# Mainboard_-_Prototype_1.net
KiCad netlist of a schematic drawn in EAGLE
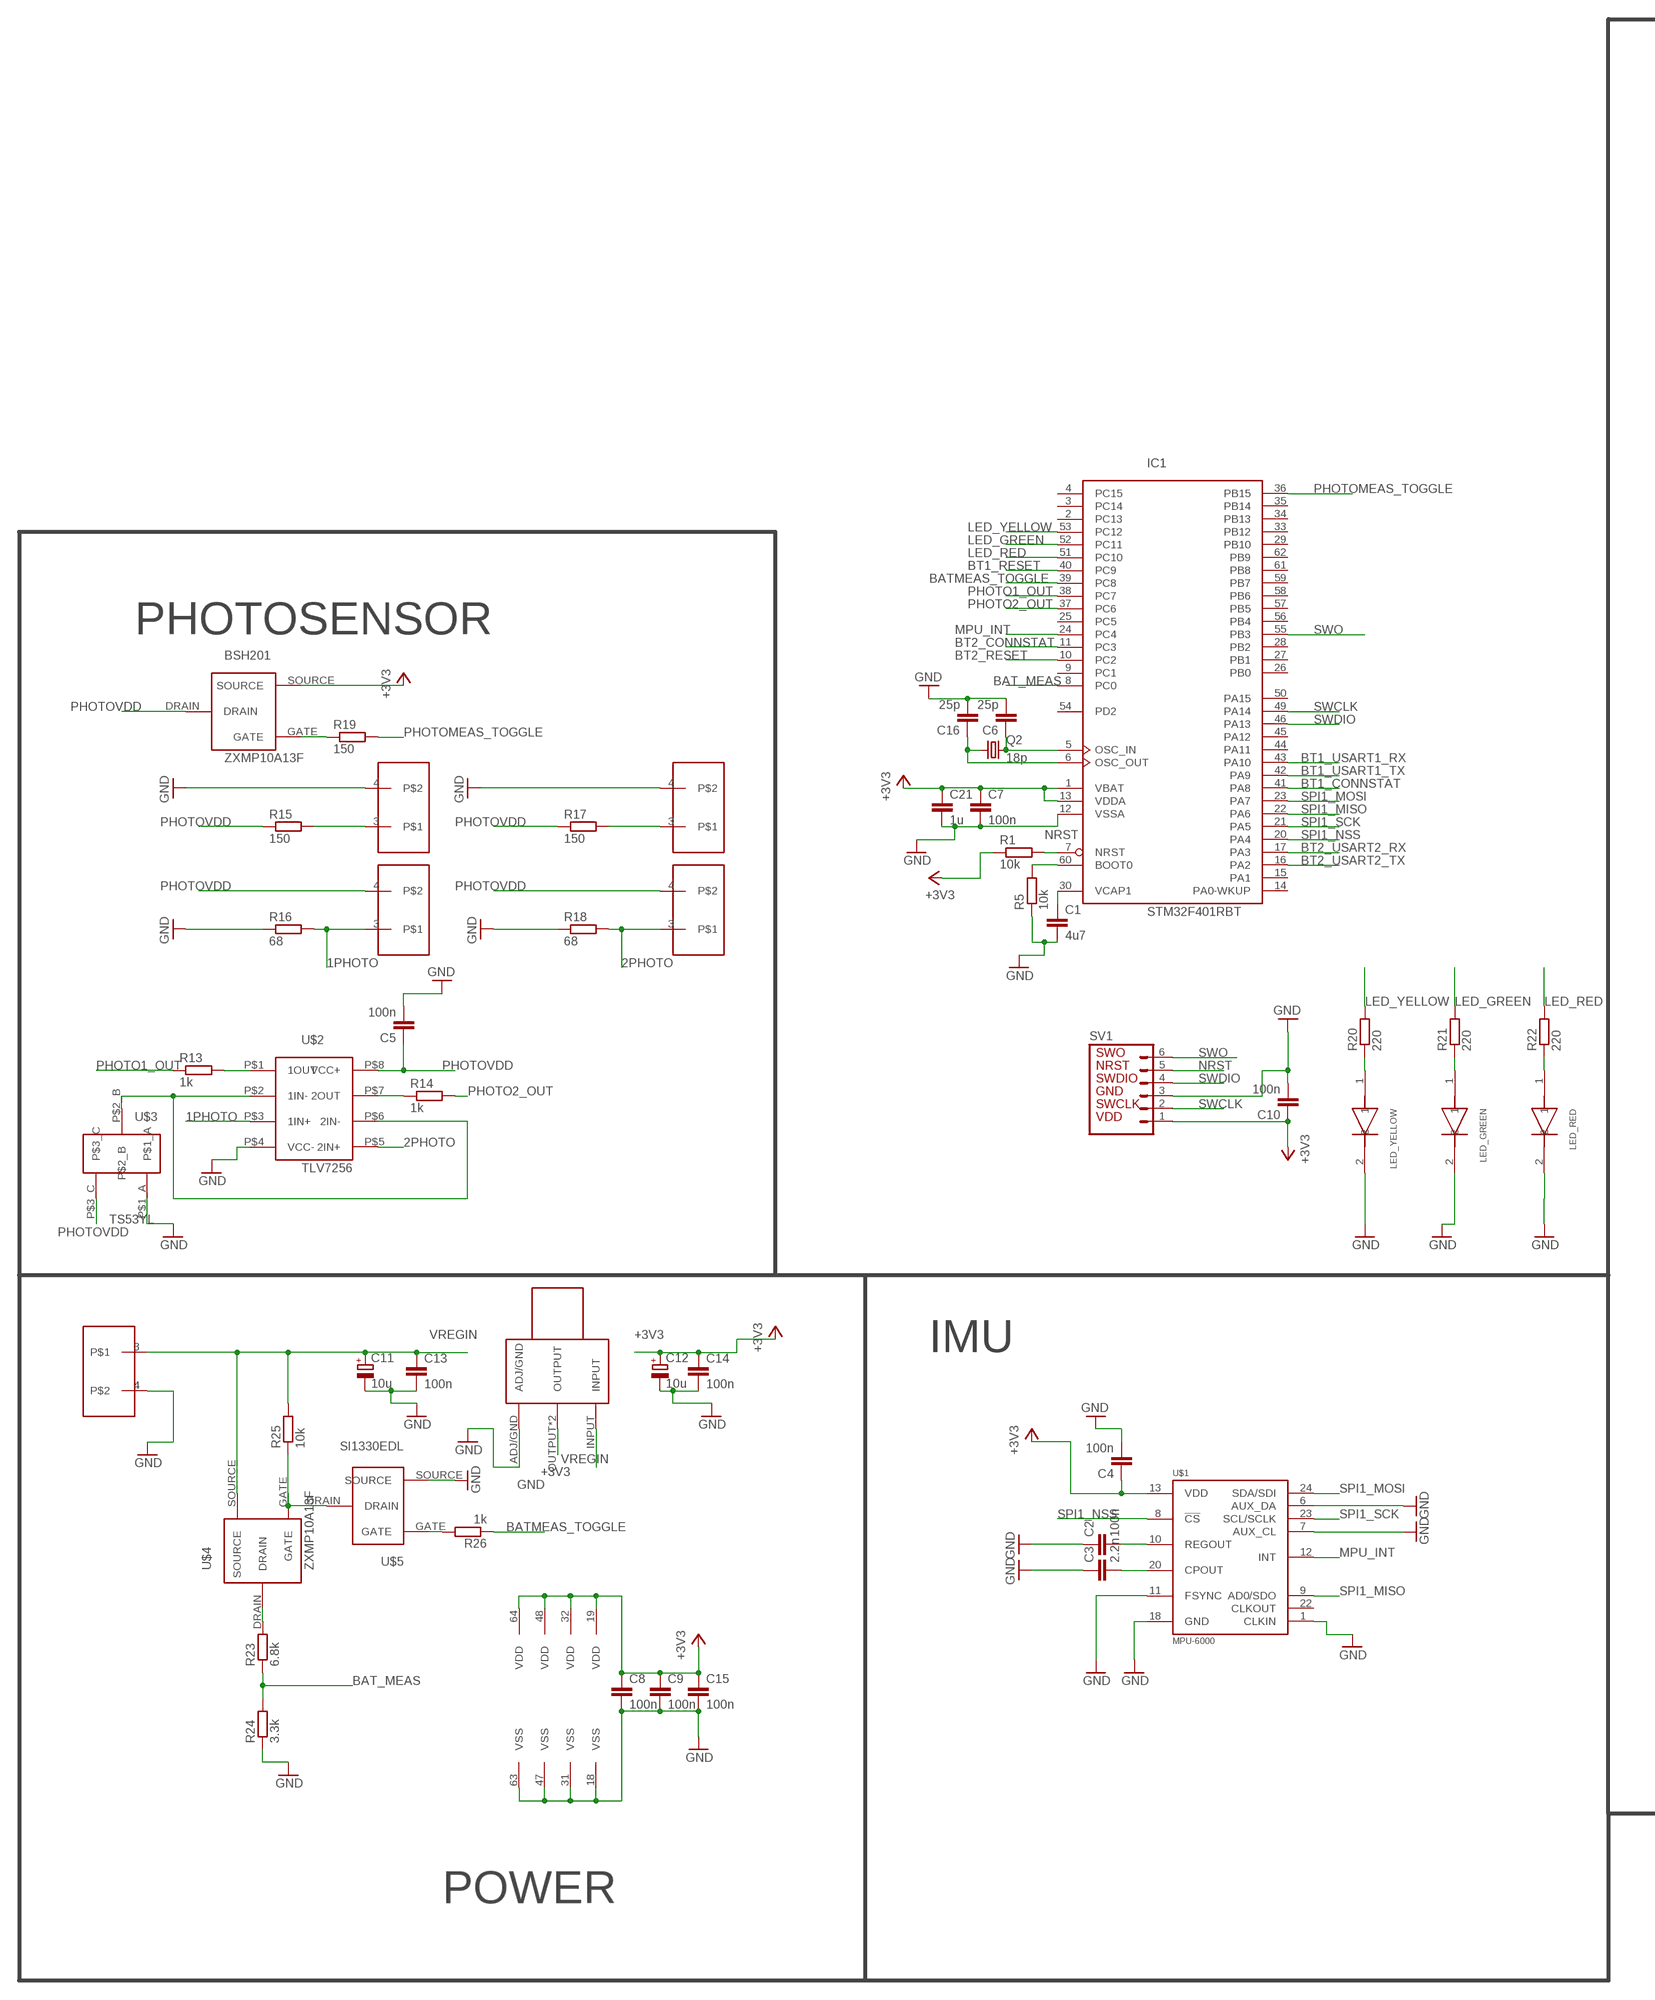
[diagram p0: schematic, sheet 1, part 1 of 2]
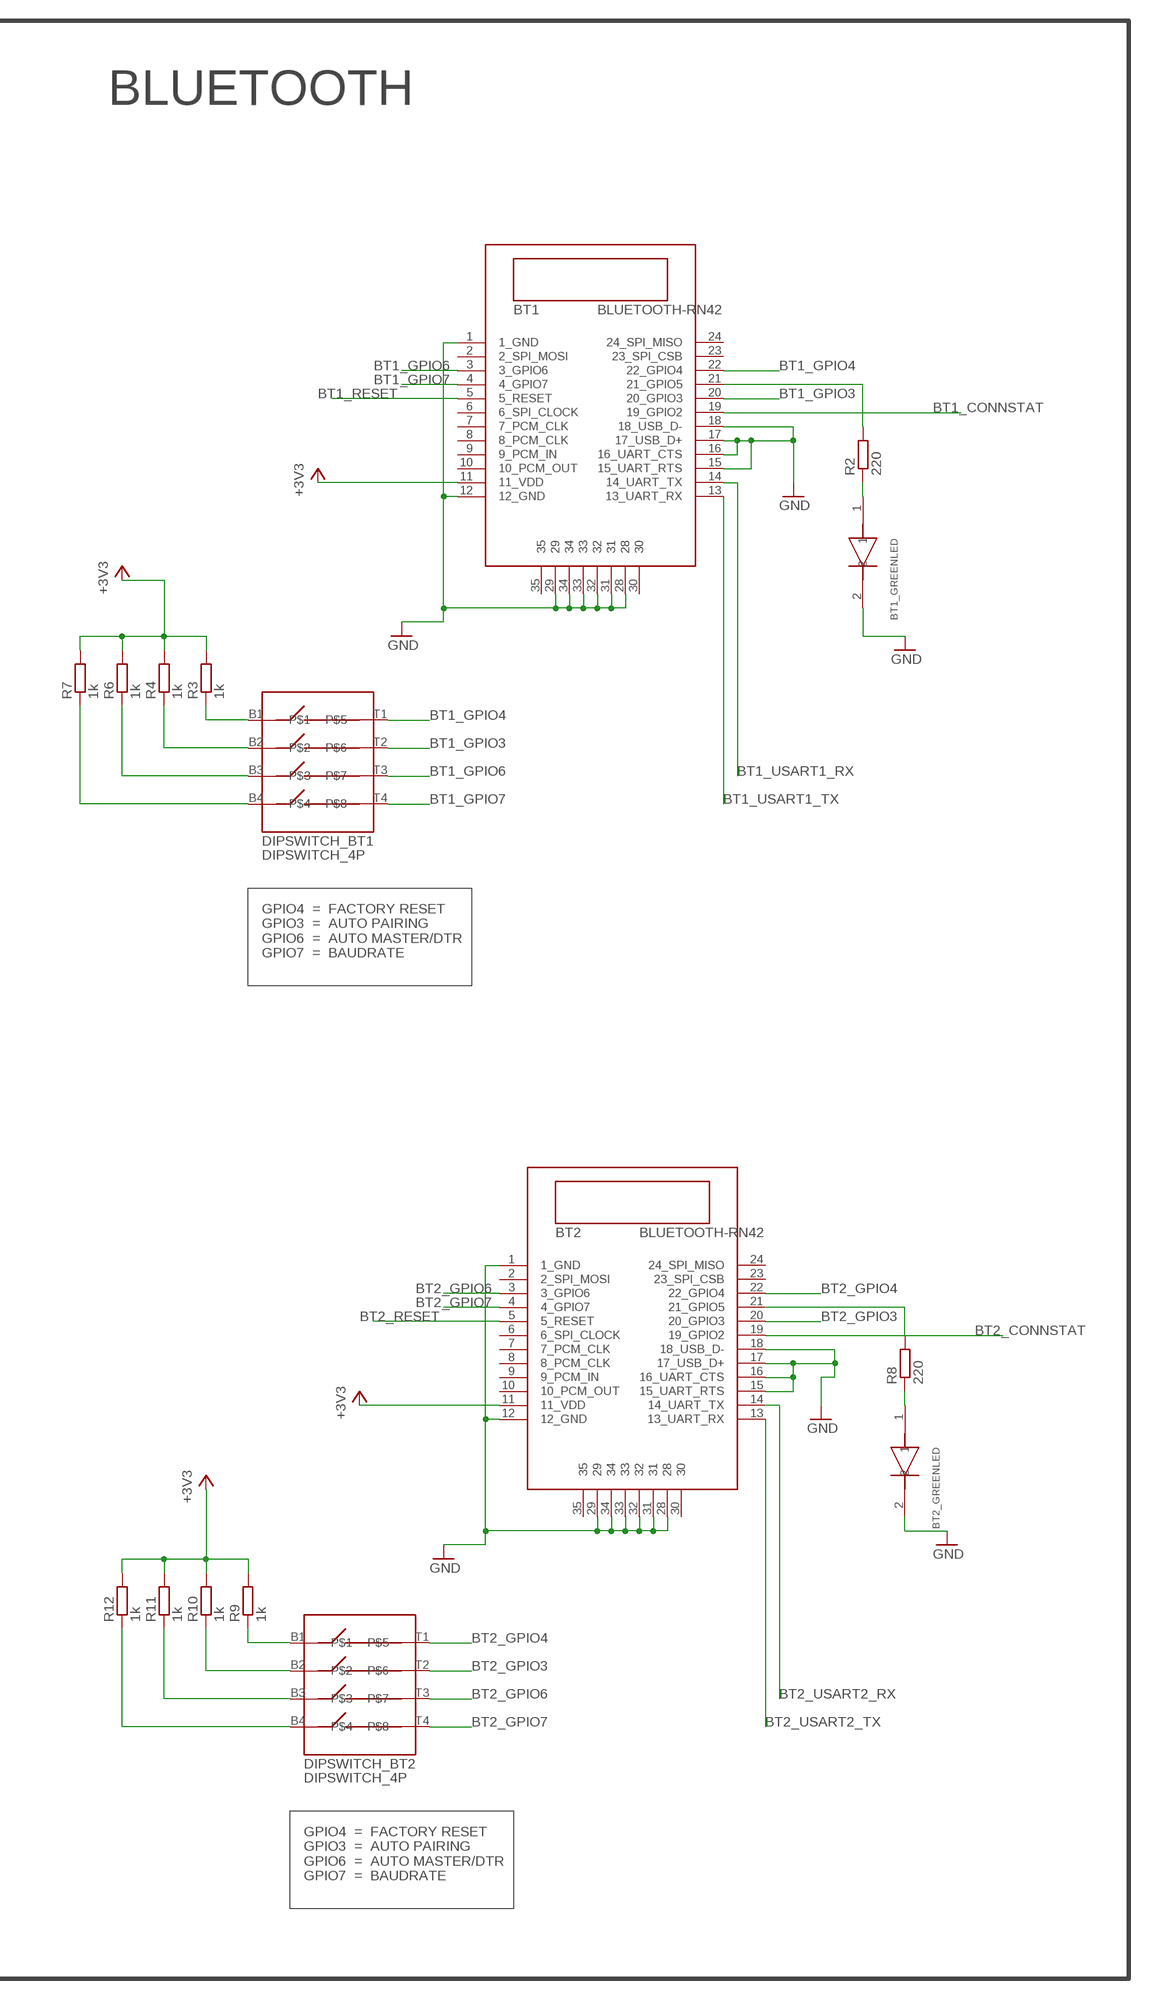
[diagram p1: schematic, sheet 1, part 2 of 2]

(export (version "E")
  (design (tool "Eeschema 10.0.6"))
  (components
    (comp (ref "BSH201")
      (value "ZXMP10A13F")
      (footprint "eagle-import:P-CHANNEL")
      (libsource (lib "eagle-import") (part "ZXMP10A13F"))
    )
    (comp (ref "BT1")
      (value "BLUETOOTH-RN42")
      (footprint "eagle-import:RN42")
      (libsource (lib "eagle-import") (part "BLUETOOTH-RN42"))
    )
    (comp (ref "BT1_GREENLED")
      (value "SMD_LED")
      (footprint "eagle-import:SMD_LED_CUSTOM")
      (libsource (lib "eagle-import") (part "SMD_LED"))
    )
    (comp (ref "BT2")
      (value "BLUETOOTH-RN42")
      (footprint "eagle-import:RN42")
      (libsource (lib "eagle-import") (part "BLUETOOTH-RN42"))
    )
    (comp (ref "BT2_GREENLED")
      (value "SMD_LED")
      (footprint "eagle-import:SMD_LED_CUSTOM")
      (libsource (lib "eagle-import") (part "SMD_LED"))
    )
    (comp (ref "C1")
      (value "4u7")
      (footprint "eagle-import:C0805")
      (libsource (lib "eagle-import") (part "C-EUC0805"))
    )
    (comp (ref "C2")
      (value "100n")
      (footprint "eagle-import:C0805")
      (libsource (lib "eagle-import") (part "C-EUC0805"))
    )
    (comp (ref "C3")
      (value "2.2n")
      (footprint "eagle-import:C0805")
      (libsource (lib "eagle-import") (part "C-EUC0805"))
    )
    (comp (ref "C4")
      (value "100n")
      (footprint "eagle-import:C0805")
      (libsource (lib "eagle-import") (part "C-EUC0805"))
    )
    (comp (ref "C5")
      (value "100n")
      (footprint "eagle-import:C0805")
      (libsource (lib "eagle-import") (part "C-EUC0805"))
    )
    (comp (ref "C6")
      (value "25p")
      (footprint "eagle-import:C0805")
      (libsource (lib "eagle-import") (part "C-EUC0805"))
    )
    (comp (ref "C7")
      (value "100n")
      (footprint "eagle-import:C0805")
      (libsource (lib "eagle-import") (part "C-EUC0805"))
    )
    (comp (ref "C8")
      (value "100n")
      (footprint "eagle-import:C0805")
      (libsource (lib "eagle-import") (part "C-EUC0805"))
    )
    (comp (ref "C9")
      (value "100n")
      (footprint "eagle-import:C0805")
      (libsource (lib "eagle-import") (part "C-EUC0805"))
    )
    (comp (ref "C10")
      (value "100n")
      (footprint "eagle-import:C0805")
      (libsource (lib "eagle-import") (part "C-EUC0805"))
    )
    (comp (ref "C11")
      (value "10u")
      (footprint "eagle-import:153CLV-0505")
      (libsource (lib "eagle-import") (part "CPOL-EU153CLV-0505"))
    )
    (comp (ref "C12")
      (value "10u")
      (footprint "eagle-import:153CLV-0505")
      (libsource (lib "eagle-import") (part "CPOL-EU153CLV-0505"))
    )
    (comp (ref "C13")
      (value "100n")
      (footprint "eagle-import:C0805")
      (libsource (lib "eagle-import") (part "C-EUC0805"))
    )
    (comp (ref "C14")
      (value "100n")
      (footprint "eagle-import:C0805")
      (libsource (lib "eagle-import") (part "C-EUC0805"))
    )
    (comp (ref "C15")
      (value "100n")
      (footprint "eagle-import:C0805")
      (libsource (lib "eagle-import") (part "C-EUC0805"))
    )
    (comp (ref "C16")
      (value "25p")
      (footprint "eagle-import:C0805")
      (libsource (lib "eagle-import") (part "C-EUC0805"))
    )
    (comp (ref "C21")
      (value "1u")
      (footprint "eagle-import:C0805")
      (libsource (lib "eagle-import") (part "C-EUC0805"))
    )
    (comp (ref "DIPSWITCH_BT1")
      (value "DIPSWITCH_4P")
      (footprint "eagle-import:DIPSWITCH4P")
      (libsource (lib "eagle-import") (part "DIPSWITCH_4P"))
    )
    (comp (ref "DIPSWITCH_BT2")
      (value "DIPSWITCH_4P")
      (footprint "eagle-import:DIPSWITCH4P")
      (libsource (lib "eagle-import") (part "DIPSWITCH_4P"))
    )
    (comp (ref "IC1")
      (value "STM32F401RBT")
      (footprint "eagle-import:LQFP64")
      (libsource (lib "eagle-import") (part "STM32F401RTB"))
    )
    (comp (ref "LED_GREEN")
      (value "SMD_LED")
      (footprint "eagle-import:SMD_LED_CUSTOM")
      (libsource (lib "eagle-import") (part "SMD_LED"))
    )
    (comp (ref "LED_RED")
      (value "SMD_LED")
      (footprint "eagle-import:SMD_LED_CUSTOM")
      (libsource (lib "eagle-import") (part "SMD_LED"))
    )
    (comp (ref "LED_YELLOW")
      (value "SMD_LED")
      (footprint "eagle-import:SMD_LED_CUSTOM")
      (libsource (lib "eagle-import") (part "SMD_LED"))
    )
    (comp (ref "LM1117-1")
      (value "LM1117")
      (footprint "eagle-import:LM1117")
      (libsource (lib "eagle-import") (part "LM1117"))
    )
    (comp (ref "Q2")
      (value "18p")
      (footprint "eagle-import:HC49UP")
      (libsource (lib "eagle-import") (part "CRYSTALHC49UP"))
    )
    (comp (ref "R1")
      (value "10k")
      (footprint "eagle-import:R0805")
      (libsource (lib "eagle-import") (part "R-EU_R0805"))
    )
    (comp (ref "R2")
      (value "220")
      (footprint "eagle-import:R0805")
      (libsource (lib "eagle-import") (part "resistor_R-EU_R0805"))
    )
    (comp (ref "R3")
      (value "1k")
      (footprint "eagle-import:R0805")
      (libsource (lib "eagle-import") (part "resistor_R-EU_R0805"))
    )
    (comp (ref "R4")
      (value "1k")
      (footprint "eagle-import:R0805")
      (libsource (lib "eagle-import") (part "resistor_R-EU_R0805"))
    )
    (comp (ref "R5")
      (value "10k")
      (footprint "eagle-import:R0805")
      (libsource (lib "eagle-import") (part "R-EU_R0805"))
    )
    (comp (ref "R6")
      (value "1k")
      (footprint "eagle-import:R0805")
      (libsource (lib "eagle-import") (part "resistor_R-EU_R0805"))
    )
    (comp (ref "R7")
      (value "1k")
      (footprint "eagle-import:R0805")
      (libsource (lib "eagle-import") (part "resistor_R-EU_R0805"))
    )
    (comp (ref "R8")
      (value "220")
      (footprint "eagle-import:R0805")
      (libsource (lib "eagle-import") (part "resistor_R-EU_R0805"))
    )
    (comp (ref "R9")
      (value "1k")
      (footprint "eagle-import:R0805")
      (libsource (lib "eagle-import") (part "resistor_R-EU_R0805"))
    )
    (comp (ref "R10")
      (value "1k")
      (footprint "eagle-import:R0805")
      (libsource (lib "eagle-import") (part "resistor_R-EU_R0805"))
    )
    (comp (ref "R11")
      (value "1k")
      (footprint "eagle-import:R0805")
      (libsource (lib "eagle-import") (part "resistor_R-EU_R0805"))
    )
    (comp (ref "R12")
      (value "1k")
      (footprint "eagle-import:R0805")
      (libsource (lib "eagle-import") (part "resistor_R-EU_R0805"))
    )
    (comp (ref "R13")
      (value "1k")
      (footprint "eagle-import:R0805")
      (libsource (lib "eagle-import") (part "R-EU_R0805"))
    )
    (comp (ref "R14")
      (value "1k")
      (footprint "eagle-import:R0805")
      (libsource (lib "eagle-import") (part "R-EU_R0805"))
    )
    (comp (ref "R15")
      (value "150")
      (footprint "eagle-import:R0805")
      (libsource (lib "eagle-import") (part "R-EU_R0805"))
    )
    (comp (ref "R16")
      (value "68")
      (footprint "eagle-import:R0805")
      (libsource (lib "eagle-import") (part "R-EU_R0805"))
    )
    (comp (ref "R17")
      (value "150")
      (footprint "eagle-import:R0805")
      (libsource (lib "eagle-import") (part "R-EU_R0805"))
    )
    (comp (ref "R18")
      (value "68")
      (footprint "eagle-import:R0805")
      (libsource (lib "eagle-import") (part "R-EU_R0805"))
    )
    (comp (ref "R19")
      (value "150")
      (footprint "eagle-import:R0805")
      (libsource (lib "eagle-import") (part "R-EU_R0805"))
    )
    (comp (ref "R20")
      (value "220")
      (footprint "eagle-import:R0805")
      (libsource (lib "eagle-import") (part "resistor_R-EU_R0805"))
    )
    (comp (ref "R21")
      (value "220")
      (footprint "eagle-import:R0805")
      (libsource (lib "eagle-import") (part "resistor_R-EU_R0805"))
    )
    (comp (ref "R22")
      (value "220")
      (footprint "eagle-import:R0805")
      (libsource (lib "eagle-import") (part "resistor_R-EU_R0805"))
    )
    (comp (ref "R23")
      (value "6.8k")
      (footprint "eagle-import:R0805")
      (libsource (lib "eagle-import") (part "R-EU_R0805"))
    )
    (comp (ref "R24")
      (value "3.3k")
      (footprint "eagle-import:R0805")
      (libsource (lib "eagle-import") (part "R-EU_R0805"))
    )
    (comp (ref "R25")
      (value "10k")
      (footprint "eagle-import:R0805")
      (libsource (lib "eagle-import") (part "R-EU_R0805"))
    )
    (comp (ref "R26")
      (value "1k")
      (footprint "eagle-import:R0805")
      (libsource (lib "eagle-import") (part "R-EU_R0805"))
    )
    (comp (ref "SKRUVPLINT_2P1")
      (value "SKRUVPLINT_2P")
      (footprint "eagle-import:SKRUVPLINT_2P")
      (libsource (lib "eagle-import") (part "SKRUVPLINT_2P"))
    )
    (comp (ref "SKRUVPLINT_2P2")
      (value "SKRUVPLINT_2P")
      (footprint "eagle-import:SKRUVPLINT_2P")
      (libsource (lib "eagle-import") (part "SKRUVPLINT_2P"))
    )
    (comp (ref "SKRUVPLINT_2P3")
      (value "SKRUVPLINT_2P")
      (footprint "eagle-import:SKRUVPLINT_2P")
      (libsource (lib "eagle-import") (part "SKRUVPLINT_2P"))
    )
    (comp (ref "SKRUVPLINT_2P4")
      (value "SKRUVPLINT_2P")
      (footprint "eagle-import:SKRUVPLINT_2P")
      (libsource (lib "eagle-import") (part "SKRUVPLINT_2P"))
    )
    (comp (ref "SKRUVPLINT_2P5")
      (value "SKRUVPLINT_2P")
      (footprint "eagle-import:SKRUVPLINT_2P")
      (libsource (lib "eagle-import") (part "SKRUVPLINT_2P"))
    )
    (comp (ref "SV1")
      (value "MA06-1")
      (footprint "eagle-import:MA06-1")
      (libsource (lib "eagle-import") (part "MA06-1"))
    )
    (comp (ref "U$1")
      (value "MPU-6000")
      (footprint "eagle-import:QFN-24")
      (fields (field (name "MF") "InvenSense"))
      (libsource (lib "eagle-import") (part "MPU-6000"))
    )
    (comp (ref "U$2")
      (value "TLV7256")
      (footprint "eagle-import:VSSOP")
      (libsource (lib "eagle-import") (part "TLV7256"))
    )
    (comp (ref "U$3")
      (value "TS53YL")
      (footprint "eagle-import:POT")
      (libsource (lib "eagle-import") (part "TS53YL"))
    )
    (comp (ref "U$4")
      (value "ZXMP10A13F")
      (footprint "eagle-import:P-CHANNEL")
      (libsource (lib "eagle-import") (part "ZXMP10A13F"))
    )
    (comp (ref "U$5")
      (value "SI1330EDL")
      (footprint "eagle-import:SOT-323")
      (libsource (lib "eagle-import") (part "SI1330EDL"))
    )
  )
  (nets
    (net (code "1") (name "+3V3") (class "Default")
      (node (ref "BSH201") (pin "SOURCE") (pinfunction "SOURCE_SOURCE") (pintype "bidirectional"))
      (node (ref "BT1") (pin "11") (pinfunction "11_VDD_11") (pintype "bidirectional"))
      (node (ref "BT2") (pin "11") (pinfunction "11_VDD_11") (pintype "bidirectional"))
      (node (ref "C10") (pin "1") (pinfunction "1_1") (pintype "passive"))
      (node (ref "C12") (pin "+") (pinfunction "+_+") (pintype "passive"))
      (node (ref "C14") (pin "1") (pinfunction "1_1") (pintype "passive"))
      (node (ref "C15") (pin "1") (pinfunction "1_1") (pintype "passive"))
      (node (ref "C21") (pin "1") (pinfunction "1_1") (pintype "passive"))
      (node (ref "C4") (pin "1") (pinfunction "1_1") (pintype "passive"))
      (node (ref "C7") (pin "1") (pinfunction "1_1") (pintype "passive"))
      (node (ref "C8") (pin "1") (pinfunction "1_1") (pintype "passive"))
      (node (ref "C9") (pin "1") (pinfunction "1_1") (pintype "passive"))
      (node (ref "IC1") (pin "1") (pinfunction "VBAT_1") (pintype "power_in"))
      (node (ref "IC1") (pin "13") (pinfunction "VDDA_13") (pintype "power_in"))
      (node (ref "IC1") (pin "19") (pinfunction "VDD_19") (pintype "power_in"))
      (node (ref "IC1") (pin "32") (pinfunction "VDD_32") (pintype "power_in"))
      (node (ref "IC1") (pin "48") (pinfunction "VDD_48") (pintype "power_in"))
      (node (ref "IC1") (pin "64") (pinfunction "VDD_64") (pintype "power_in"))
      (node (ref "LM1117-1") (pin "OUTPUT") (pinfunction "OUTPUT_OUTPUT") (pintype "bidirectional"))
      (node (ref "LM1117-1") (pin "OUTPUT2") (pinfunction "OUTPUT_OUTPUT2") (pintype "bidirectional"))
      (node (ref "R1") (pin "1") (pinfunction "1_1") (pintype "passive"))
      (node (ref "R10") (pin "2") (pinfunction "2_2") (pintype "passive"))
      (node (ref "R11") (pin "2") (pinfunction "2_2") (pintype "passive"))
      (node (ref "R12") (pin "2") (pinfunction "2_2") (pintype "passive"))
      (node (ref "R3") (pin "2") (pinfunction "2_2") (pintype "passive"))
      (node (ref "R4") (pin "2") (pinfunction "2_2") (pintype "passive"))
      (node (ref "R6") (pin "2") (pinfunction "2_2") (pintype "passive"))
      (node (ref "R7") (pin "2") (pinfunction "2_2") (pintype "passive"))
      (node (ref "R9") (pin "2") (pinfunction "2_2") (pintype "passive"))
      (node (ref "SV1") (pin "1") (pinfunction "1_1") (pintype "passive"))
      (node (ref "U$1") (pin "13") (pinfunction "VDD_13") (pintype "bidirectional"))
    )
    (net (code "2") (name "/1PHOTO") (class "Default")
      (node (ref "R16") (pin "2") (pinfunction "2_2") (pintype "passive"))
      (node (ref "SKRUVPLINT_2P2") (pin "3") (pinfunction "P$1_3") (pintype "bidirectional"))
      (node (ref "U$2") (pin "P$3") (pinfunction "1IN+_P$3") (pintype "bidirectional"))
    )
    (net (code "3") (name "/2PHOTO") (class "Default")
      (node (ref "R18") (pin "2") (pinfunction "2_2") (pintype "passive"))
      (node (ref "SKRUVPLINT_2P4") (pin "3") (pinfunction "P$1_3") (pintype "bidirectional"))
      (node (ref "U$2") (pin "P$5") (pinfunction "2IN+_P$5") (pintype "bidirectional"))
    )
    (net (code "4") (name "/BATMEAS_TOGGLE") (class "Default")
      (node (ref "IC1") (pin "39") (pinfunction "PC8_39") (pintype "bidirectional"))
      (node (ref "R26") (pin "1") (pinfunction "1_1") (pintype "passive"))
    )
    (net (code "5") (name "/BAT_MEAS") (class "Default")
      (node (ref "IC1") (pin "8") (pinfunction "PC0_8") (pintype "bidirectional"))
      (node (ref "R23") (pin "1") (pinfunction "1_1") (pintype "passive"))
      (node (ref "R24") (pin "2") (pinfunction "2_2") (pintype "passive"))
    )
    (net (code "6") (name "/BT1_CONNSTAT") (class "Default")
      (node (ref "BT1") (pin "19") (pinfunction "19_GPIO2_19") (pintype "bidirectional"))
      (node (ref "IC1") (pin "41") (pinfunction "PA8_41") (pintype "bidirectional"))
    )
    (net (code "7") (name "/BT1_GPIO3") (class "Default")
      (node (ref "BT1") (pin "20") (pinfunction "20_GPIO3_20") (pintype "bidirectional"))
      (node (ref "DIPSWITCH_BT1") (pin "T2") (pinfunction "P$6_T2") (pintype "bidirectional"))
    )
    (net (code "8") (name "/BT1_GPIO4") (class "Default")
      (node (ref "BT1") (pin "22") (pinfunction "22_GPIO4_22") (pintype "bidirectional"))
      (node (ref "DIPSWITCH_BT1") (pin "T1") (pinfunction "P$5_T1") (pintype "bidirectional"))
    )
    (net (code "9") (name "/BT1_GPIO6") (class "Default")
      (node (ref "BT1") (pin "3") (pinfunction "3_GPIO6_3") (pintype "bidirectional"))
      (node (ref "DIPSWITCH_BT1") (pin "T3") (pinfunction "P$7_T3") (pintype "bidirectional"))
    )
    (net (code "10") (name "/BT1_GPIO7") (class "Default")
      (node (ref "BT1") (pin "4") (pinfunction "4_GPIO7_4") (pintype "bidirectional"))
      (node (ref "DIPSWITCH_BT1") (pin "T4") (pinfunction "P$8_T4") (pintype "bidirectional"))
    )
    (net (code "11") (name "/BT1_RESET") (class "Default")
      (node (ref "BT1") (pin "5") (pinfunction "5_RESET_5") (pintype "bidirectional"))
      (node (ref "IC1") (pin "40") (pinfunction "PC9_40") (pintype "bidirectional"))
    )
    (net (code "12") (name "/BT1_USART1_RX") (class "Default")
      (node (ref "BT1") (pin "14") (pinfunction "14_UART_TX_14") (pintype "bidirectional"))
      (node (ref "IC1") (pin "43") (pinfunction "PA10_43") (pintype "bidirectional"))
    )
    (net (code "13") (name "/BT1_USART1_TX") (class "Default")
      (node (ref "BT1") (pin "13") (pinfunction "13_UART_RX_13") (pintype "bidirectional"))
      (node (ref "IC1") (pin "42") (pinfunction "PA9_42") (pintype "bidirectional"))
    )
    (net (code "14") (name "/BT2_CONNSTAT") (class "Default")
      (node (ref "BT2") (pin "19") (pinfunction "19_GPIO2_19") (pintype "bidirectional"))
      (node (ref "IC1") (pin "11") (pinfunction "PC3_11") (pintype "bidirectional"))
    )
    (net (code "15") (name "/BT2_GPIO3") (class "Default")
      (node (ref "BT2") (pin "20") (pinfunction "20_GPIO3_20") (pintype "bidirectional"))
      (node (ref "DIPSWITCH_BT2") (pin "T2") (pinfunction "P$6_T2") (pintype "bidirectional"))
    )
    (net (code "16") (name "/BT2_GPIO4") (class "Default")
      (node (ref "BT2") (pin "22") (pinfunction "22_GPIO4_22") (pintype "bidirectional"))
      (node (ref "DIPSWITCH_BT2") (pin "T1") (pinfunction "P$5_T1") (pintype "bidirectional"))
    )
    (net (code "17") (name "/BT2_GPIO6") (class "Default")
      (node (ref "BT2") (pin "3") (pinfunction "3_GPIO6_3") (pintype "bidirectional"))
      (node (ref "DIPSWITCH_BT2") (pin "T3") (pinfunction "P$7_T3") (pintype "bidirectional"))
    )
    (net (code "18") (name "/BT2_GPIO7") (class "Default")
      (node (ref "BT2") (pin "4") (pinfunction "4_GPIO7_4") (pintype "bidirectional"))
      (node (ref "DIPSWITCH_BT2") (pin "T4") (pinfunction "P$8_T4") (pintype "bidirectional"))
    )
    (net (code "19") (name "/BT2_RESET") (class "Default")
      (node (ref "BT2") (pin "5") (pinfunction "5_RESET_5") (pintype "bidirectional"))
      (node (ref "IC1") (pin "10") (pinfunction "PC2_10") (pintype "bidirectional"))
    )
    (net (code "20") (name "/BT2_USART2_RX") (class "Default")
      (node (ref "BT2") (pin "14") (pinfunction "14_UART_TX_14") (pintype "bidirectional"))
      (node (ref "IC1") (pin "17") (pinfunction "PA3_17") (pintype "bidirectional"))
    )
    (net (code "21") (name "/BT2_USART2_TX") (class "Default")
      (node (ref "BT2") (pin "13") (pinfunction "13_UART_RX_13") (pintype "bidirectional"))
      (node (ref "IC1") (pin "16") (pinfunction "PA2_16") (pintype "bidirectional"))
    )
    (net (code "22") (name "/LED_GREEN") (class "Default")
      (node (ref "IC1") (pin "52") (pinfunction "PC11_52") (pintype "bidirectional"))
      (node (ref "R21") (pin "2") (pinfunction "2_2") (pintype "passive"))
    )
    (net (code "23") (name "/LED_RED") (class "Default")
      (node (ref "IC1") (pin "51") (pinfunction "PC10_51") (pintype "bidirectional"))
      (node (ref "R22") (pin "2") (pinfunction "2_2") (pintype "passive"))
    )
    (net (code "24") (name "/LED_YELLOW") (class "Default")
      (node (ref "IC1") (pin "53") (pinfunction "PC12_53") (pintype "bidirectional"))
      (node (ref "R20") (pin "2") (pinfunction "2_2") (pintype "passive"))
    )
    (net (code "25") (name "/MPU_INT") (class "Default")
      (node (ref "IC1") (pin "24") (pinfunction "PC4_24") (pintype "bidirectional"))
      (node (ref "U$1") (pin "12") (pinfunction "INT_12") (pintype "bidirectional"))
    )
    (net (code "26") (name "/NRST") (class "Default")
      (node (ref "IC1") (pin "7") (pinfunction "NRST_7") (pintype "bidirectional"))
      (node (ref "R1") (pin "2") (pinfunction "2_2") (pintype "passive"))
      (node (ref "SV1") (pin "5") (pinfunction "5_5") (pintype "passive"))
    )
    (net (code "27") (name "/PHOTO1_OUT") (class "Default")
      (node (ref "IC1") (pin "38") (pinfunction "PC7_38") (pintype "bidirectional"))
      (node (ref "R13") (pin "1") (pinfunction "1_1") (pintype "passive"))
    )
    (net (code "28") (name "/PHOTO2_OUT") (class "Default")
      (node (ref "IC1") (pin "37") (pinfunction "PC6_37") (pintype "bidirectional"))
      (node (ref "R14") (pin "2") (pinfunction "2_2") (pintype "passive"))
    )
    (net (code "29") (name "/PHOTOMEAS_TOGGLE") (class "Default")
      (node (ref "IC1") (pin "36") (pinfunction "PB15_36") (pintype "bidirectional"))
      (node (ref "R19") (pin "2") (pinfunction "2_2") (pintype "passive"))
    )
    (net (code "30") (name "/PHOTOVDD") (class "Default")
      (node (ref "BSH201") (pin "DRAIN") (pinfunction "DRAIN_DRAIN") (pintype "bidirectional"))
      (node (ref "C5") (pin "1") (pinfunction "1_1") (pintype "passive"))
      (node (ref "R15") (pin "1") (pinfunction "1_1") (pintype "passive"))
      (node (ref "R17") (pin "1") (pinfunction "1_1") (pintype "passive"))
      (node (ref "SKRUVPLINT_2P2") (pin "4") (pinfunction "P$2_4") (pintype "bidirectional"))
      (node (ref "SKRUVPLINT_2P4") (pin "4") (pinfunction "P$2_4") (pintype "bidirectional"))
      (node (ref "U$2") (pin "P$8") (pinfunction "VCC+_P$8") (pintype "bidirectional"))
      (node (ref "U$3") (pin "P$3_C") (pinfunction "P$3_C_P$3_C") (pintype "bidirectional"))
    )
    (net (code "31") (name "/SPI1_MISO") (class "Default")
      (node (ref "IC1") (pin "22") (pinfunction "PA6_22") (pintype "bidirectional"))
      (node (ref "U$1") (pin "9") (pinfunction "AD0/SDO_9") (pintype "bidirectional"))
    )
    (net (code "32") (name "/SPI1_MOSI") (class "Default")
      (node (ref "IC1") (pin "23") (pinfunction "PA7_23") (pintype "bidirectional"))
      (node (ref "U$1") (pin "24") (pinfunction "SDA/SDI_24") (pintype "bidirectional"))
    )
    (net (code "33") (name "/SPI1_NSS") (class "Default")
      (node (ref "IC1") (pin "20") (pinfunction "PA4_20") (pintype "bidirectional"))
      (node (ref "U$1") (pin "8") (pinfunction "~{CS}_8") (pintype "bidirectional"))
    )
    (net (code "34") (name "/SPI1_SCK") (class "Default")
      (node (ref "IC1") (pin "21") (pinfunction "PA5_21") (pintype "bidirectional"))
      (node (ref "U$1") (pin "23") (pinfunction "SCL/SCLK_23") (pintype "bidirectional"))
    )
    (net (code "35") (name "/SWCLK") (class "Default")
      (node (ref "IC1") (pin "49") (pinfunction "PA14_49") (pintype "bidirectional"))
      (node (ref "SV1") (pin "2") (pinfunction "2_2") (pintype "passive"))
    )
    (net (code "36") (name "/SWDIO") (class "Default")
      (node (ref "IC1") (pin "46") (pinfunction "PA13_46") (pintype "bidirectional"))
      (node (ref "SV1") (pin "4") (pinfunction "4_4") (pintype "passive"))
    )
    (net (code "37") (name "/SWO") (class "Default")
      (node (ref "IC1") (pin "55") (pinfunction "PB3_55") (pintype "bidirectional"))
      (node (ref "SV1") (pin "6") (pinfunction "6_6") (pintype "passive"))
    )
    (net (code "38") (name "/VREGIN") (class "Default")
      (node (ref "C11") (pin "+") (pinfunction "+_+") (pintype "passive"))
      (node (ref "C13") (pin "1") (pinfunction "1_1") (pintype "passive"))
      (node (ref "LM1117-1") (pin "INPUT") (pinfunction "INPUT_INPUT") (pintype "bidirectional"))
      (node (ref "R25") (pin "2") (pinfunction "2_2") (pintype "passive"))
      (node (ref "SKRUVPLINT_2P5") (pin "3") (pinfunction "P$1_3") (pintype "bidirectional"))
      (node (ref "U$4") (pin "SOURCE") (pinfunction "SOURCE_SOURCE") (pintype "bidirectional"))
    )
    (net (code "39") (name "GND") (class "Default")
      (node (ref "BT1") (pin "1") (pinfunction "1_GND_1") (pintype "bidirectional"))
      (node (ref "BT1") (pin "12") (pinfunction "12_GND_12") (pintype "bidirectional"))
      (node (ref "BT1") (pin "15") (pinfunction "15_UART_RTS_15") (pintype "bidirectional"))
      (node (ref "BT1") (pin "16") (pinfunction "16_UART_CTS_16") (pintype "bidirectional"))
      (node (ref "BT1") (pin "17") (pinfunction "17_USB_D+_17") (pintype "bidirectional"))
      (node (ref "BT1") (pin "18") (pinfunction "18_USB_D-_18") (pintype "bidirectional"))
      (node (ref "BT1") (pin "28") (pinfunction "28_28") (pintype "bidirectional"))
      (node (ref "BT1") (pin "29") (pinfunction "29_29") (pintype "bidirectional"))
      (node (ref "BT1") (pin "31") (pinfunction "31_31") (pintype "bidirectional"))
      (node (ref "BT1") (pin "32") (pinfunction "32_32") (pintype "bidirectional"))
      (node (ref "BT1") (pin "33") (pinfunction "33_33") (pintype "bidirectional"))
      (node (ref "BT1") (pin "34") (pinfunction "34_34") (pintype "bidirectional"))
      (node (ref "BT1_GREENLED") (pin "2") (pinfunction "2_2") (pintype "bidirectional"))
      (node (ref "BT2") (pin "1") (pinfunction "1_GND_1") (pintype "bidirectional"))
      (node (ref "BT2") (pin "12") (pinfunction "12_GND_12") (pintype "bidirectional"))
      (node (ref "BT2") (pin "15") (pinfunction "15_UART_RTS_15") (pintype "bidirectional"))
      (node (ref "BT2") (pin "16") (pinfunction "16_UART_CTS_16") (pintype "bidirectional"))
      (node (ref "BT2") (pin "17") (pinfunction "17_USB_D+_17") (pintype "bidirectional"))
      (node (ref "BT2") (pin "18") (pinfunction "18_USB_D-_18") (pintype "bidirectional"))
      (node (ref "BT2") (pin "28") (pinfunction "28_28") (pintype "bidirectional"))
      (node (ref "BT2") (pin "29") (pinfunction "29_29") (pintype "bidirectional"))
      (node (ref "BT2") (pin "31") (pinfunction "31_31") (pintype "bidirectional"))
      (node (ref "BT2") (pin "32") (pinfunction "32_32") (pintype "bidirectional"))
      (node (ref "BT2") (pin "33") (pinfunction "33_33") (pintype "bidirectional"))
      (node (ref "BT2") (pin "34") (pinfunction "34_34") (pintype "bidirectional"))
      (node (ref "BT2_GREENLED") (pin "2") (pinfunction "2_2") (pintype "bidirectional"))
      (node (ref "C1") (pin "2") (pinfunction "2_2") (pintype "passive"))
      (node (ref "C10") (pin "2") (pinfunction "2_2") (pintype "passive"))
      (node (ref "C11") (pin "-") (pinfunction "-_-") (pintype "passive"))
      (node (ref "C12") (pin "-") (pinfunction "-_-") (pintype "passive"))
      (node (ref "C13") (pin "2") (pinfunction "2_2") (pintype "passive"))
      (node (ref "C14") (pin "2") (pinfunction "2_2") (pintype "passive"))
      (node (ref "C15") (pin "2") (pinfunction "2_2") (pintype "passive"))
      (node (ref "C16") (pin "2") (pinfunction "2_2") (pintype "passive"))
      (node (ref "C2") (pin "1") (pinfunction "1_1") (pintype "passive"))
      (node (ref "C21") (pin "2") (pinfunction "2_2") (pintype "passive"))
      (node (ref "C3") (pin "1") (pinfunction "1_1") (pintype "passive"))
      (node (ref "C4") (pin "2") (pinfunction "2_2") (pintype "passive"))
      (node (ref "C5") (pin "2") (pinfunction "2_2") (pintype "passive"))
      (node (ref "C6") (pin "2") (pinfunction "2_2") (pintype "passive"))
      (node (ref "C7") (pin "2") (pinfunction "2_2") (pintype "passive"))
      (node (ref "C8") (pin "2") (pinfunction "2_2") (pintype "passive"))
      (node (ref "C9") (pin "2") (pinfunction "2_2") (pintype "passive"))
      (node (ref "IC1") (pin "12") (pinfunction "VSSA_12") (pintype "power_in"))
      (node (ref "IC1") (pin "18") (pinfunction "VSS_18") (pintype "power_in"))
      (node (ref "IC1") (pin "31") (pinfunction "VSS_31") (pintype "power_in"))
      (node (ref "IC1") (pin "47") (pinfunction "VSS_47") (pintype "power_in"))
      (node (ref "IC1") (pin "63") (pinfunction "VSS_63") (pintype "power_in"))
      (node (ref "LED_GREEN") (pin "2") (pinfunction "2_2") (pintype "bidirectional"))
      (node (ref "LED_RED") (pin "2") (pinfunction "2_2") (pintype "bidirectional"))
      (node (ref "LED_YELLOW") (pin "2") (pinfunction "2_2") (pintype "bidirectional"))
      (node (ref "LM1117-1") (pin "ADJ/GND") (pinfunction "ADJ/GND_ADJ/GND") (pintype "bidirectional"))
      (node (ref "R16") (pin "1") (pinfunction "1_1") (pintype "passive"))
      (node (ref "R18") (pin "1") (pinfunction "1_1") (pintype "passive"))
      (node (ref "R24") (pin "1") (pinfunction "1_1") (pintype "passive"))
      (node (ref "R5") (pin "1") (pinfunction "1_1") (pintype "passive"))
      (node (ref "SKRUVPLINT_2P1") (pin "4") (pinfunction "P$2_4") (pintype "bidirectional"))
      (node (ref "SKRUVPLINT_2P3") (pin "4") (pinfunction "P$2_4") (pintype "bidirectional"))
      (node (ref "SKRUVPLINT_2P5") (pin "4") (pinfunction "P$2_4") (pintype "bidirectional"))
      (node (ref "SV1") (pin "3") (pinfunction "3_3") (pintype "passive"))
      (node (ref "U$1") (pin "1") (pinfunction "CLKIN_1") (pintype "bidirectional"))
      (node (ref "U$1") (pin "11") (pinfunction "FSYNC_11") (pintype "bidirectional"))
      (node (ref "U$1") (pin "18") (pinfunction "GND_18") (pintype "bidirectional"))
      (node (ref "U$1") (pin "6") (pinfunction "AUX_DA_6") (pintype "bidirectional"))
      (node (ref "U$1") (pin "7") (pinfunction "AUX_CL_7") (pintype "bidirectional"))
      (node (ref "U$2") (pin "P$4") (pinfunction "VCC-_P$4") (pintype "bidirectional"))
      (node (ref "U$3") (pin "P$1_A") (pinfunction "P$1_A_P$1_A") (pintype "bidirectional"))
      (node (ref "U$5") (pin "SOURCE") (pinfunction "SOURCE_SOURCE") (pintype "bidirectional"))
    )
    (net (code "40") (name "Net-(BSH201-PadGATE)") (class "Default")
      (node (ref "BSH201") (pin "GATE") (pinfunction "GATE_GATE") (pintype "bidirectional"))
      (node (ref "R19") (pin "1") (pinfunction "1_1") (pintype "passive"))
    )
    (net (code "41") (name "Net-(BT1-21_GPIO5)") (class "Default")
      (node (ref "BT1") (pin "21") (pinfunction "21_GPIO5_21") (pintype "bidirectional"))
      (node (ref "R2") (pin "2") (pinfunction "2_2") (pintype "passive"))
    )
    (net (code "42") (name "Net-(BT1_GREENLED-Pad1)") (class "Default")
      (node (ref "BT1_GREENLED") (pin "1") (pinfunction "1_1") (pintype "bidirectional"))
      (node (ref "R2") (pin "1") (pinfunction "1_1") (pintype "passive"))
    )
    (net (code "43") (name "Net-(BT2-21_GPIO5)") (class "Default")
      (node (ref "BT2") (pin "21") (pinfunction "21_GPIO5_21") (pintype "bidirectional"))
      (node (ref "R8") (pin "2") (pinfunction "2_2") (pintype "passive"))
    )
    (net (code "44") (name "Net-(BT2_GREENLED-Pad1)") (class "Default")
      (node (ref "BT2_GREENLED") (pin "1") (pinfunction "1_1") (pintype "bidirectional"))
      (node (ref "R8") (pin "1") (pinfunction "1_1") (pintype "passive"))
    )
    (net (code "45") (name "Net-(DIPSWITCH_BT1-P$1)") (class "Default")
      (node (ref "DIPSWITCH_BT1") (pin "B1") (pinfunction "P$1_B1") (pintype "bidirectional"))
      (node (ref "R3") (pin "1") (pinfunction "1_1") (pintype "passive"))
    )
    (net (code "46") (name "Net-(DIPSWITCH_BT1-P$2)") (class "Default")
      (node (ref "DIPSWITCH_BT1") (pin "B2") (pinfunction "P$2_B2") (pintype "bidirectional"))
      (node (ref "R4") (pin "1") (pinfunction "1_1") (pintype "passive"))
    )
    (net (code "47") (name "Net-(DIPSWITCH_BT1-P$3)") (class "Default")
      (node (ref "DIPSWITCH_BT1") (pin "B3") (pinfunction "P$3_B3") (pintype "bidirectional"))
      (node (ref "R6") (pin "1") (pinfunction "1_1") (pintype "passive"))
    )
    (net (code "48") (name "Net-(DIPSWITCH_BT1-P$4)") (class "Default")
      (node (ref "DIPSWITCH_BT1") (pin "B4") (pinfunction "P$4_B4") (pintype "bidirectional"))
      (node (ref "R7") (pin "1") (pinfunction "1_1") (pintype "passive"))
    )
    (net (code "49") (name "Net-(DIPSWITCH_BT2-P$1)") (class "Default")
      (node (ref "DIPSWITCH_BT2") (pin "B1") (pinfunction "P$1_B1") (pintype "bidirectional"))
      (node (ref "R9") (pin "1") (pinfunction "1_1") (pintype "passive"))
    )
    (net (code "50") (name "Net-(DIPSWITCH_BT2-P$2)") (class "Default")
      (node (ref "DIPSWITCH_BT2") (pin "B2") (pinfunction "P$2_B2") (pintype "bidirectional"))
      (node (ref "R10") (pin "1") (pinfunction "1_1") (pintype "passive"))
    )
    (net (code "51") (name "Net-(DIPSWITCH_BT2-P$3)") (class "Default")
      (node (ref "DIPSWITCH_BT2") (pin "B3") (pinfunction "P$3_B3") (pintype "bidirectional"))
      (node (ref "R11") (pin "1") (pinfunction "1_1") (pintype "passive"))
    )
    (net (code "52") (name "Net-(DIPSWITCH_BT2-P$4)") (class "Default")
      (node (ref "DIPSWITCH_BT2") (pin "B4") (pinfunction "P$4_B4") (pintype "bidirectional"))
      (node (ref "R12") (pin "1") (pinfunction "1_1") (pintype "passive"))
    )
    (net (code "53") (name "Net-(IC1A-BOOT0)") (class "Default")
      (node (ref "IC1") (pin "60") (pinfunction "BOOT0_60") (pintype "input"))
      (node (ref "R5") (pin "2") (pinfunction "2_2") (pintype "passive"))
    )
    (net (code "54") (name "Net-(IC1A-OSC_IN)") (class "Default")
      (node (ref "C6") (pin "1") (pinfunction "1_1") (pintype "passive"))
      (node (ref "IC1") (pin "5") (pinfunction "OSC_IN_5") (pintype "bidirectional"))
      (node (ref "Q2") (pin "2") (pinfunction "2_2") (pintype "passive"))
    )
    (net (code "55") (name "Net-(IC1A-OSC_OUT)") (class "Default")
      (node (ref "C16") (pin "1") (pinfunction "1_1") (pintype "passive"))
      (node (ref "IC1") (pin "6") (pinfunction "OSC_OUT_6") (pintype "bidirectional"))
      (node (ref "Q2") (pin "1") (pinfunction "1_1") (pintype "passive"))
    )
    (net (code "56") (name "Net-(IC1A-VCAP1)") (class "Default")
      (node (ref "C1") (pin "1") (pinfunction "1_1") (pintype "passive"))
      (node (ref "IC1") (pin "30") (pinfunction "VCAP1_30") (pintype "power_in"))
    )
    (net (code "57") (name "Net-(LED_GREEN-Pad1)") (class "Default")
      (node (ref "LED_GREEN") (pin "1") (pinfunction "1_1") (pintype "bidirectional"))
      (node (ref "R21") (pin "1") (pinfunction "1_1") (pintype "passive"))
    )
    (net (code "58") (name "Net-(LED_RED-Pad1)") (class "Default")
      (node (ref "LED_RED") (pin "1") (pinfunction "1_1") (pintype "bidirectional"))
      (node (ref "R22") (pin "1") (pinfunction "1_1") (pintype "passive"))
    )
    (net (code "59") (name "Net-(LED_YELLOW-Pad1)") (class "Default")
      (node (ref "LED_YELLOW") (pin "1") (pinfunction "1_1") (pintype "bidirectional"))
      (node (ref "R20") (pin "1") (pinfunction "1_1") (pintype "passive"))
    )
    (net (code "60") (name "Net-(R23-Pad2)") (class "Default")
      (node (ref "R23") (pin "2") (pinfunction "2_2") (pintype "passive"))
      (node (ref "U$4") (pin "DRAIN") (pinfunction "DRAIN_DRAIN") (pintype "bidirectional"))
    )
    (net (code "61") (name "Net-(R25-Pad1)") (class "Default")
      (node (ref "R25") (pin "1") (pinfunction "1_1") (pintype "passive"))
      (node (ref "U$4") (pin "GATE") (pinfunction "GATE_GATE") (pintype "bidirectional"))
      (node (ref "U$5") (pin "DRAIN") (pinfunction "DRAIN_DRAIN") (pintype "bidirectional"))
    )
    (net (code "62") (name "Net-(R26-Pad2)") (class "Default")
      (node (ref "R26") (pin "2") (pinfunction "2_2") (pintype "passive"))
      (node (ref "U$5") (pin "GATE") (pinfunction "GATE_GATE") (pintype "bidirectional"))
    )
    (net (code "63") (name "Net-(SKRUVPLINT_2P1-P$1)") (class "Default")
      (node (ref "R15") (pin "2") (pinfunction "2_2") (pintype "passive"))
      (node (ref "SKRUVPLINT_2P1") (pin "3") (pinfunction "P$1_3") (pintype "bidirectional"))
    )
    (net (code "64") (name "Net-(SKRUVPLINT_2P3-P$1)") (class "Default")
      (node (ref "R17") (pin "2") (pinfunction "2_2") (pintype "passive"))
      (node (ref "SKRUVPLINT_2P3") (pin "3") (pinfunction "P$1_3") (pintype "bidirectional"))
    )
    (net (code "65") (name "Net-(U$1-CPOUT)") (class "Default")
      (node (ref "C3") (pin "2") (pinfunction "2_2") (pintype "passive"))
      (node (ref "U$1") (pin "20") (pinfunction "CPOUT_20") (pintype "bidirectional"))
    )
    (net (code "66") (name "Net-(U$1-REGOUT)") (class "Default")
      (node (ref "C2") (pin "2") (pinfunction "2_2") (pintype "passive"))
      (node (ref "U$1") (pin "10") (pinfunction "REGOUT_10") (pintype "bidirectional"))
    )
    (net (code "67") (name "Net-(U$2-1IN-)") (class "Default")
      (node (ref "U$2") (pin "P$2") (pinfunction "1IN-_P$2") (pintype "bidirectional"))
      (node (ref "U$2") (pin "P$6") (pinfunction "2IN-_P$6") (pintype "bidirectional"))
      (node (ref "U$3") (pin "P$2_B") (pinfunction "P$2_B_P$2_B") (pintype "bidirectional"))
    )
    (net (code "68") (name "Net-(U$2-1OUT)") (class "Default")
      (node (ref "R13") (pin "2") (pinfunction "2_2") (pintype "passive"))
      (node (ref "U$2") (pin "P$1") (pinfunction "1OUT_P$1") (pintype "bidirectional"))
    )
    (net (code "69") (name "Net-(U$2-2OUT)") (class "Default")
      (node (ref "R14") (pin "1") (pinfunction "1_1") (pintype "passive"))
      (node (ref "U$2") (pin "P$7") (pinfunction "2OUT_P$7") (pintype "bidirectional"))
    )
    (net (code "70") (name "unconnected-(BT1-2_SPI_MOSI-Pad2)") (class "Default")
      (node (ref "BT1") (pin "2") (pinfunction "2_SPI_MOSI_2") (pintype "bidirectional"))
    )
    (net (code "71") (name "unconnected-(BT1-6_SPI_CLOCK-Pad6)") (class "Default")
      (node (ref "BT1") (pin "6") (pinfunction "6_SPI_CLOCK_6") (pintype "bidirectional"))
    )
    (net (code "72") (name "unconnected-(BT1-7_PCM_CLK-Pad7)") (class "Default")
      (node (ref "BT1") (pin "7") (pinfunction "7_PCM_CLK_7") (pintype "bidirectional"))
    )
    (net (code "73") (name "unconnected-(BT1-8_PCM_CLK-Pad8)") (class "Default")
      (node (ref "BT1") (pin "8") (pinfunction "8_PCM_CLK_8") (pintype "bidirectional"))
    )
    (net (code "74") (name "unconnected-(BT1-9_PCM_IN-Pad9)") (class "Default")
      (node (ref "BT1") (pin "9") (pinfunction "9_PCM_IN_9") (pintype "bidirectional"))
    )
    (net (code "75") (name "unconnected-(BT1-10_PCM_OUT-Pad10)") (class "Default")
      (node (ref "BT1") (pin "10") (pinfunction "10_PCM_OUT_10") (pintype "bidirectional"))
    )
    (net (code "76") (name "unconnected-(BT1-23_SPI_CSB-Pad23)") (class "Default")
      (node (ref "BT1") (pin "23") (pinfunction "23_SPI_CSB_23") (pintype "bidirectional"))
    )
    (net (code "77") (name "unconnected-(BT1-24_SPI_MISO-Pad24)") (class "Default")
      (node (ref "BT1") (pin "24") (pinfunction "24_SPI_MISO_24") (pintype "bidirectional"))
    )
    (net (code "78") (name "unconnected-(BT1-Pad30)") (class "Default")
      (node (ref "BT1") (pin "30") (pinfunction "30_30") (pintype "bidirectional"))
    )
    (net (code "79") (name "unconnected-(BT1-Pad35)") (class "Default")
      (node (ref "BT1") (pin "35") (pinfunction "35_35") (pintype "bidirectional"))
    )
    (net (code "80") (name "unconnected-(BT2-2_SPI_MOSI-Pad2)") (class "Default")
      (node (ref "BT2") (pin "2") (pinfunction "2_SPI_MOSI_2") (pintype "bidirectional"))
    )
    (net (code "81") (name "unconnected-(BT2-6_SPI_CLOCK-Pad6)") (class "Default")
      (node (ref "BT2") (pin "6") (pinfunction "6_SPI_CLOCK_6") (pintype "bidirectional"))
    )
    (net (code "82") (name "unconnected-(BT2-7_PCM_CLK-Pad7)") (class "Default")
      (node (ref "BT2") (pin "7") (pinfunction "7_PCM_CLK_7") (pintype "bidirectional"))
    )
    (net (code "83") (name "unconnected-(BT2-8_PCM_CLK-Pad8)") (class "Default")
      (node (ref "BT2") (pin "8") (pinfunction "8_PCM_CLK_8") (pintype "bidirectional"))
    )
    (net (code "84") (name "unconnected-(BT2-9_PCM_IN-Pad9)") (class "Default")
      (node (ref "BT2") (pin "9") (pinfunction "9_PCM_IN_9") (pintype "bidirectional"))
    )
    (net (code "85") (name "unconnected-(BT2-10_PCM_OUT-Pad10)") (class "Default")
      (node (ref "BT2") (pin "10") (pinfunction "10_PCM_OUT_10") (pintype "bidirectional"))
    )
    (net (code "86") (name "unconnected-(BT2-23_SPI_CSB-Pad23)") (class "Default")
      (node (ref "BT2") (pin "23") (pinfunction "23_SPI_CSB_23") (pintype "bidirectional"))
    )
    (net (code "87") (name "unconnected-(BT2-24_SPI_MISO-Pad24)") (class "Default")
      (node (ref "BT2") (pin "24") (pinfunction "24_SPI_MISO_24") (pintype "bidirectional"))
    )
    (net (code "88") (name "unconnected-(BT2-Pad30)") (class "Default")
      (node (ref "BT2") (pin "30") (pinfunction "30_30") (pintype "bidirectional"))
    )
    (net (code "89") (name "unconnected-(BT2-Pad35)") (class "Default")
      (node (ref "BT2") (pin "35") (pinfunction "35_35") (pintype "bidirectional"))
    )
    (net (code "90") (name "unconnected-(IC1A-PA0-WKUP-Pad14)") (class "Default")
      (node (ref "IC1") (pin "14") (pinfunction "PA0-WKUP_14") (pintype "bidirectional"))
    )
    (net (code "91") (name "unconnected-(IC1A-PA1-Pad15)") (class "Default")
      (node (ref "IC1") (pin "15") (pinfunction "PA1_15") (pintype "bidirectional"))
    )
    (net (code "92") (name "unconnected-(IC1A-PA11-Pad44)") (class "Default")
      (node (ref "IC1") (pin "44") (pinfunction "PA11_44") (pintype "bidirectional"))
    )
    (net (code "93") (name "unconnected-(IC1A-PA12-Pad45)") (class "Default")
      (node (ref "IC1") (pin "45") (pinfunction "PA12_45") (pintype "bidirectional"))
    )
    (net (code "94") (name "unconnected-(IC1A-PA15-Pad50)") (class "Default")
      (node (ref "IC1") (pin "50") (pinfunction "PA15_50") (pintype "bidirectional"))
    )
    (net (code "95") (name "unconnected-(IC1A-PB0-Pad26)") (class "Default")
      (node (ref "IC1") (pin "26") (pinfunction "PB0_26") (pintype "bidirectional"))
    )
    (net (code "96") (name "unconnected-(IC1A-PB1-Pad27)") (class "Default")
      (node (ref "IC1") (pin "27") (pinfunction "PB1_27") (pintype "bidirectional"))
    )
    (net (code "97") (name "unconnected-(IC1A-PB2-Pad28)") (class "Default")
      (node (ref "IC1") (pin "28") (pinfunction "PB2_28") (pintype "bidirectional"))
    )
    (net (code "98") (name "unconnected-(IC1A-PB4-Pad56)") (class "Default")
      (node (ref "IC1") (pin "56") (pinfunction "PB4_56") (pintype "bidirectional"))
    )
    (net (code "99") (name "unconnected-(IC1A-PB5-Pad57)") (class "Default")
      (node (ref "IC1") (pin "57") (pinfunction "PB5_57") (pintype "bidirectional"))
    )
    (net (code "100") (name "unconnected-(IC1A-PB6-Pad58)") (class "Default")
      (node (ref "IC1") (pin "58") (pinfunction "PB6_58") (pintype "bidirectional"))
    )
    (net (code "101") (name "unconnected-(IC1A-PB7-Pad59)") (class "Default")
      (node (ref "IC1") (pin "59") (pinfunction "PB7_59") (pintype "bidirectional"))
    )
    (net (code "102") (name "unconnected-(IC1A-PB8-Pad61)") (class "Default")
      (node (ref "IC1") (pin "61") (pinfunction "PB8_61") (pintype "bidirectional"))
    )
    (net (code "103") (name "unconnected-(IC1A-PB9-Pad62)") (class "Default")
      (node (ref "IC1") (pin "62") (pinfunction "PB9_62") (pintype "bidirectional"))
    )
    (net (code "104") (name "unconnected-(IC1A-PB10-Pad29)") (class "Default")
      (node (ref "IC1") (pin "29") (pinfunction "PB10_29") (pintype "bidirectional"))
    )
    (net (code "105") (name "unconnected-(IC1A-PB12-Pad33)") (class "Default")
      (node (ref "IC1") (pin "33") (pinfunction "PB12_33") (pintype "bidirectional"))
    )
    (net (code "106") (name "unconnected-(IC1A-PB13-Pad34)") (class "Default")
      (node (ref "IC1") (pin "34") (pinfunction "PB13_34") (pintype "bidirectional"))
    )
    (net (code "107") (name "unconnected-(IC1A-PB14-Pad35)") (class "Default")
      (node (ref "IC1") (pin "35") (pinfunction "PB14_35") (pintype "bidirectional"))
    )
    (net (code "108") (name "unconnected-(IC1A-PC1-Pad9)") (class "Default")
      (node (ref "IC1") (pin "9") (pinfunction "PC1_9") (pintype "bidirectional"))
    )
    (net (code "109") (name "unconnected-(IC1A-PC5-Pad25)") (class "Default")
      (node (ref "IC1") (pin "25") (pinfunction "PC5_25") (pintype "bidirectional"))
    )
    (net (code "110") (name "unconnected-(IC1A-PC13-Pad2)") (class "Default")
      (node (ref "IC1") (pin "2") (pinfunction "PC13_2") (pintype "bidirectional"))
    )
    (net (code "111") (name "unconnected-(IC1A-PC14-Pad3)") (class "Default")
      (node (ref "IC1") (pin "3") (pinfunction "PC14_3") (pintype "bidirectional"))
    )
    (net (code "112") (name "unconnected-(IC1A-PC15-Pad4)") (class "Default")
      (node (ref "IC1") (pin "4") (pinfunction "PC15_4") (pintype "bidirectional"))
    )
    (net (code "113") (name "unconnected-(IC1A-PD2-Pad54)") (class "Default")
      (node (ref "IC1") (pin "54") (pinfunction "PD2_54") (pintype "bidirectional"))
    )
    (net (code "114") (name "unconnected-(U$1-CLKOUT-Pad22)") (class "Default")
      (node (ref "U$1") (pin "22") (pinfunction "CLKOUT_22") (pintype "bidirectional"))
    )
  )
)
